# MSXII_SteeringWheelSchematic.net
KiCad netlist of a schematic drawn in Altium Designer
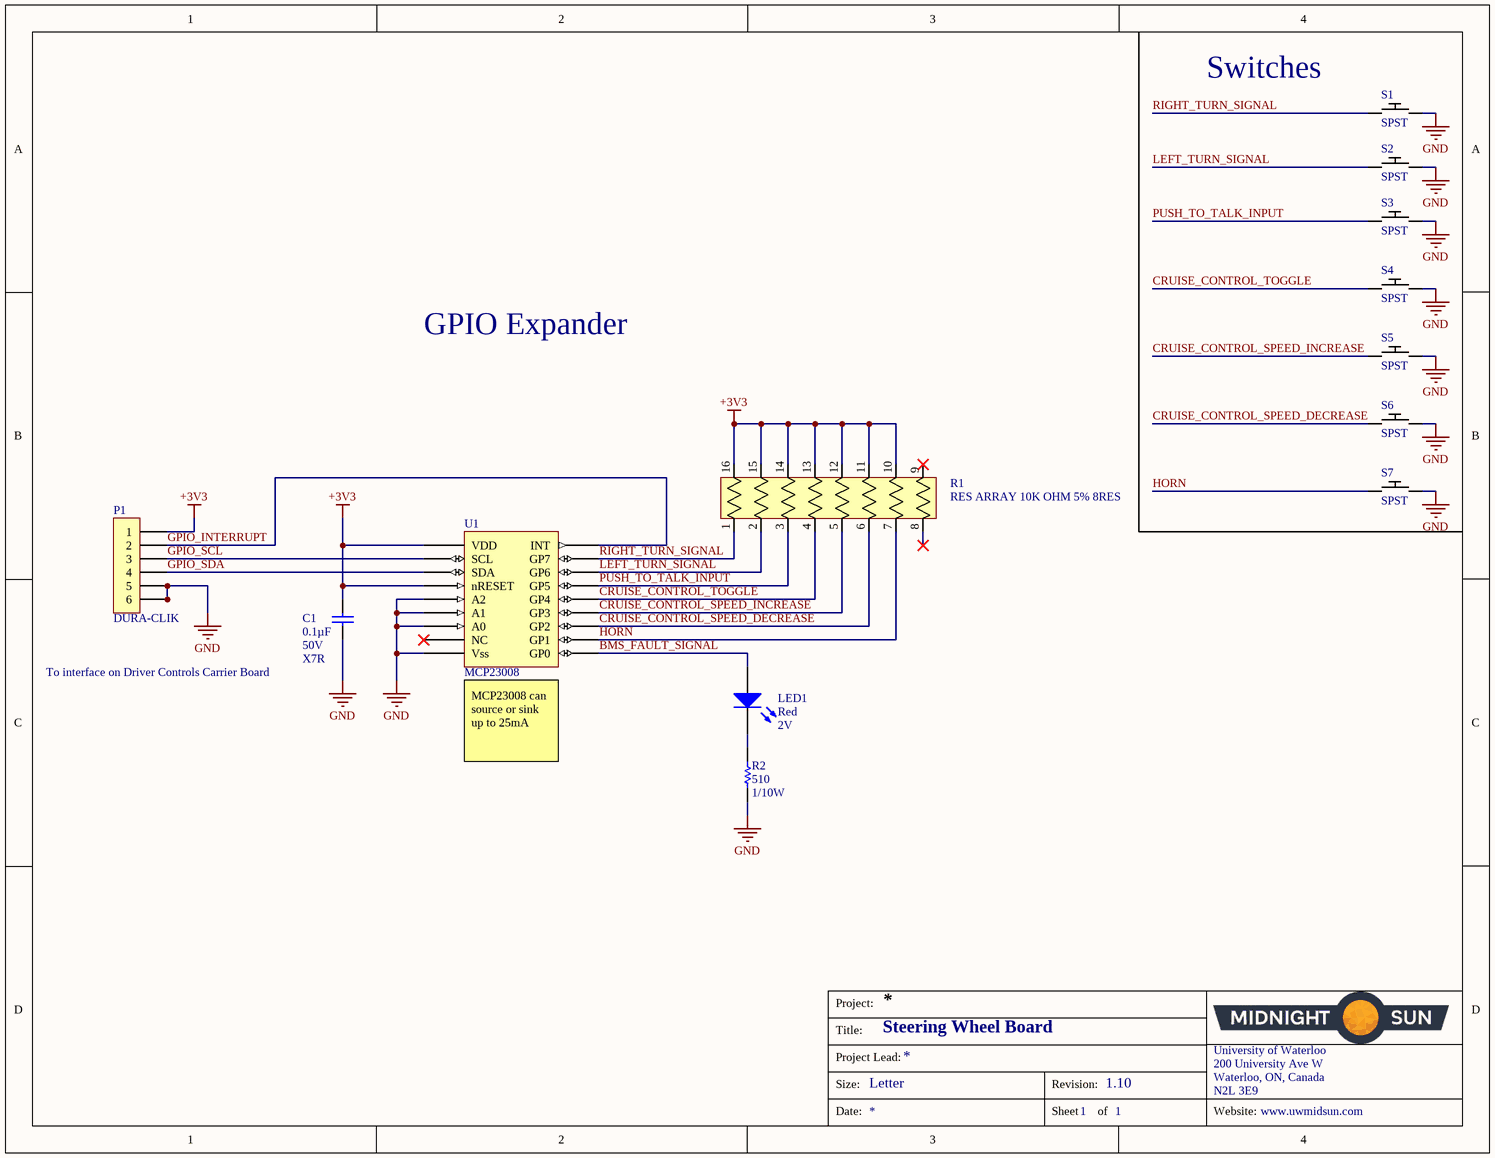
[diagram p0: MSXII_SteeringWheelSchematic.SchDoc]

(export (version "E")
  (design (tool "Eeschema 10.0.6"))
  (components
    (comp (ref "C1")
      (value "CAP CER 0.1UF 50V 10% X7R 0603")
      (footprint "CAP, 0603")
      (description "0.10µF ±10% 50V Ceramic Capacitor X7R 0603 (1608 Metric)")
      (fields
        (field (name "TOLERANCE") "±10%")
        (field (name "CAPACITANCE") "0.1µF")
        (field (name "VOLTAGE") "50V")
        (field (name "TEMPERATURE COEFFICIENT") "X7R")
      )
      (libsource (lib "Schematic Diagrams") (part "CAP CER 0.1UF 50V 10% X7R 0603"))
    )
    (comp (ref "LED1")
      (value "LED RED CLEAR 2V 0603")
      (footprint "LED_0603")
      (description "Red 631nm LED Indication - Discrete 2V 0603 (1608 Metric)")
      (fields
        (field (name "MANUFACTURER") "Wurth Electronics Inc.")
        (field (name "MANUFACTURER PART NUMBER") "150060RS75000")
        (field (name "COLOR") "Red")
        (field (name "VOLTAGE - FORWARD (VF) (TYP)") "2V")
      )
      (libsource (lib "Schematic Diagrams") (part "LED RED CLEAR 2V 0603"))
    )
    (comp (ref "P1")
      (value "DURA-CLIK")
      (footprint "CONN, 6POS DURA-CLIK VERT")
      (description "6 Positions Header, Shrouded Connector 0.079\" (2.00mm) Surface Mount, Vertical Tin")
      (fields (field (name "MANUFACTURER") "Molex") (field (name "MANUFACTURER PART NUMBER") "5600200820"))
      (libsource (lib "Schematic Diagrams") (part "CONN 6POS DURA-CLIK 0.079{dblquote}"))
    )
    (comp (ref "R1")
      (value "RES ARRAY 10K OHM 5% 8RES")
      (footprint "RES ARRAY, 8 POS 1506")
      (description "RES ARRAY SMD 10K 5% 62.5mW 1506")
      (fields
        (field (name "MANUFACTURER_PART_NUMBER") "EXB-2HV103JV")
        (field (name "MANUFACTURER") "Panasonic Electronic Components")
        (field (name "COPYRIGHT") "Copyright (C) 2015 Accelerated Designs. All rights reserved")
      )
      (libsource (lib "Schematic Diagrams") (part "RES ARRAY 10K OHM 5% 8RES EXB-2HV103JV"))
    )
    (comp (ref "R2")
      (value "RES 510 OHM 5% 1/10W 0603")
      (footprint "RES, 0603")
      (description "RES SMD 510 OHM 5% 1/10W 0603")
      (fields
        (field (name "TOLERANCE") "±5%")
        (field (name "RESISTANCE") "510")
        (field (name "POWER") "1/10W")
      )
      (libsource (lib "Schematic Diagrams") (part "RES 510 OHM 5% 1/10W 0603"))
    )
    (comp (ref "S1")
      (value "SPST")
      (footprint "SW SPST D6 SERIES")
      (description "Pushbutton Switch SPST-NO Keyswitch Through Hole D6 Series")
      (fields (field (name "MANUFACTURER") "C&K") (field (name "MANUFACTURER PART NUMBER") "D6R00 F2 LFS"))
      (libsource (lib "Schematic Diagrams") (part "SW SPST-NO 0.1A 32V D6 Series"))
    )
    (comp (ref "S2")
      (value "SPST")
      (footprint "SW SPST D6 SERIES")
      (description "Pushbutton Switch SPST-NO Keyswitch Through Hole D6 Series")
      (fields (field (name "MANUFACTURER") "C&K") (field (name "MANUFACTURER PART NUMBER") "D6R00 F2 LFS"))
      (libsource (lib "Schematic Diagrams") (part "SW SPST-NO 0.1A 32V D6 Series"))
    )
    (comp (ref "S3")
      (value "SPST")
      (footprint "SW SPST D6 SERIES")
      (description "Pushbutton Switch SPST-NO Keyswitch Through Hole D6 Series")
      (fields (field (name "MANUFACTURER") "C&K") (field (name "MANUFACTURER PART NUMBER") "D6R00 F2 LFS"))
      (libsource (lib "Schematic Diagrams") (part "SW SPST-NO 0.1A 32V D6 Series"))
    )
    (comp (ref "S4")
      (value "SPST")
      (footprint "SW SPST D6 SERIES")
      (description "Pushbutton Switch SPST-NO Keyswitch Through Hole D6 Series")
      (fields (field (name "MANUFACTURER") "C&K") (field (name "MANUFACTURER PART NUMBER") "D6R00 F2 LFS"))
      (libsource (lib "Schematic Diagrams") (part "SW SPST-NO 0.1A 32V D6 Series"))
    )
    (comp (ref "S5")
      (value "SPST")
      (footprint "SW SPST D6 SERIES")
      (description "Pushbutton Switch SPST-NO Keyswitch Through Hole D6 Series")
      (fields (field (name "MANUFACTURER") "C&K") (field (name "MANUFACTURER PART NUMBER") "D6R00 F2 LFS"))
      (libsource (lib "Schematic Diagrams") (part "SW SPST-NO 0.1A 32V D6 Series"))
    )
    (comp (ref "S6")
      (value "SPST")
      (footprint "SW SPST D6 SERIES")
      (description "Pushbutton Switch SPST-NO Keyswitch Through Hole D6 Series")
      (fields (field (name "MANUFACTURER") "C&K") (field (name "MANUFACTURER PART NUMBER") "D6R00 F2 LFS"))
      (libsource (lib "Schematic Diagrams") (part "SW SPST-NO 0.1A 32V D6 Series"))
    )
    (comp (ref "S7")
      (value "SPST")
      (footprint "SW SPST D6 SERIES")
      (description "Pushbutton Switch SPST-NO Keyswitch Through Hole D6 Series")
      (fields (field (name "MANUFACTURER") "C&K") (field (name "MANUFACTURER PART NUMBER") "D6R00 F2 LFS"))
      (libsource (lib "Schematic Diagrams") (part "SW SPST-NO 0.1A 32V D6 Series"))
    )
    (comp (ref "U1")
      (value "MCP23008")
      (footprint "IC 18SOIC")
      (description "MCP23008 I/O Expander 8B+1Int 18P SOIC")
      (fields
        (field (name "MANUFACTURER") "Microchip Technology")
        (field (name "MANUFACTURER PART NUMBER") "MCP23008T-E/SO")
      )
      (libsource (lib "Schematic Diagrams") (part "IC I/O EXPANDER I2C 8B 18SOIC"))
    )
  )
  (nets
    (net (code "1") (name "+3V3") (class "Default")
      (node (ref "C1") (pin "1") (pinfunction "1_1") (pintype "passive"))
      (node (ref "P1") (pin "1") (pinfunction "1_1") (pintype "passive"))
      (node (ref "R1") (pin "10") (pinfunction "10_10") (pintype "passive"))
      (node (ref "R1") (pin "11") (pinfunction "11_11") (pintype "passive"))
      (node (ref "R1") (pin "12") (pinfunction "12_12") (pintype "passive"))
      (node (ref "R1") (pin "13") (pinfunction "13_13") (pintype "passive"))
      (node (ref "R1") (pin "14") (pinfunction "14_14") (pintype "passive"))
      (node (ref "R1") (pin "15") (pinfunction "15_15") (pintype "passive"))
      (node (ref "R1") (pin "16") (pinfunction "16_16") (pintype "passive"))
      (node (ref "U1") (pin "18") (pinfunction "VDD_18") (pintype "power_in"))
      (node (ref "U1") (pin "6") (pinfunction "nRESET_6") (pintype "input"))
    )
    (net (code "2") (name "/BMS_FAULT_SIGNAL") (class "Default")
      (node (ref "LED1") (pin "1") (pinfunction "A_1") (pintype "passive"))
      (node (ref "U1") (pin "10") (pinfunction "GP0_10") (pintype "bidirectional"))
    )
    (net (code "3") (name "/CRUISE_CONTROL_SPEED_DECREASE") (class "Default")
      (node (ref "R1") (pin "6") (pinfunction "6_6") (pintype "passive"))
      (node (ref "S6") (pin "1") (pinfunction "1_1") (pintype "passive"))
      (node (ref "U1") (pin "12") (pinfunction "GP2_12") (pintype "bidirectional"))
    )
    (net (code "4") (name "/CRUISE_CONTROL_SPEED_INCREASE") (class "Default")
      (node (ref "R1") (pin "5") (pinfunction "5_5") (pintype "passive"))
      (node (ref "S5") (pin "1") (pinfunction "1_1") (pintype "passive"))
      (node (ref "U1") (pin "13") (pinfunction "GP3_13") (pintype "bidirectional"))
    )
    (net (code "5") (name "/CRUISE_CONTROL_TOGGLE") (class "Default")
      (node (ref "R1") (pin "4") (pinfunction "4_4") (pintype "passive"))
      (node (ref "S4") (pin "1") (pinfunction "1_1") (pintype "passive"))
      (node (ref "U1") (pin "14") (pinfunction "GP4_14") (pintype "bidirectional"))
    )
    (net (code "6") (name "/GPIO_INTERRUPT") (class "Default")
      (node (ref "P1") (pin "2") (pinfunction "2_2") (pintype "passive"))
      (node (ref "U1") (pin "8") (pinfunction "INT_8") (pintype "output"))
    )
    (net (code "7") (name "/GPIO_SCL") (class "Default")
      (node (ref "P1") (pin "3") (pinfunction "3_3") (pintype "passive"))
      (node (ref "U1") (pin "1") (pinfunction "SCL_1") (pintype "bidirectional"))
    )
    (net (code "8") (name "/GPIO_SDA") (class "Default")
      (node (ref "P1") (pin "4") (pinfunction "4_4") (pintype "passive"))
      (node (ref "U1") (pin "2") (pinfunction "SDA_2") (pintype "bidirectional"))
    )
    (net (code "9") (name "/HORN") (class "Default")
      (node (ref "R1") (pin "7") (pinfunction "7_7") (pintype "passive"))
      (node (ref "S7") (pin "1") (pinfunction "1_1") (pintype "passive"))
      (node (ref "U1") (pin "11") (pinfunction "GP1_11") (pintype "bidirectional"))
    )
    (net (code "10") (name "/LEFT_TURN_SIGNAL") (class "Default")
      (node (ref "R1") (pin "2") (pinfunction "2_2") (pintype "passive"))
      (node (ref "S2") (pin "1") (pinfunction "1_1") (pintype "passive"))
      (node (ref "U1") (pin "16") (pinfunction "GP6_16") (pintype "bidirectional"))
    )
    (net (code "11") (name "/PUSH_TO_TALK_INPUT") (class "Default")
      (node (ref "R1") (pin "3") (pinfunction "3_3") (pintype "passive"))
      (node (ref "S3") (pin "1") (pinfunction "1_1") (pintype "passive"))
      (node (ref "U1") (pin "15") (pinfunction "GP5_15") (pintype "bidirectional"))
    )
    (net (code "12") (name "/RIGHT_TURN_SIGNAL") (class "Default")
      (node (ref "R1") (pin "1") (pinfunction "1_1") (pintype "passive"))
      (node (ref "S1") (pin "1") (pinfunction "1_1") (pintype "passive"))
      (node (ref "U1") (pin "17") (pinfunction "GP7_17") (pintype "bidirectional"))
    )
    (net (code "13") (name "GND") (class "Default")
      (node (ref "C1") (pin "2") (pinfunction "2_2") (pintype "passive"))
      (node (ref "P1") (pin "5") (pinfunction "5_5") (pintype "passive"))
      (node (ref "P1") (pin "6") (pinfunction "6_6") (pintype "passive"))
      (node (ref "R2") (pin "2") (pinfunction "2_2") (pintype "passive"))
      (node (ref "S1") (pin "2") (pinfunction "2_2") (pintype "passive"))
      (node (ref "S2") (pin "2") (pinfunction "2_2") (pintype "passive"))
      (node (ref "S3") (pin "2") (pinfunction "2_2") (pintype "passive"))
      (node (ref "S4") (pin "2") (pinfunction "2_2") (pintype "passive"))
      (node (ref "S5") (pin "2") (pinfunction "2_2") (pintype "passive"))
      (node (ref "S6") (pin "2") (pinfunction "2_2") (pintype "passive"))
      (node (ref "S7") (pin "2") (pinfunction "2_2") (pintype "passive"))
      (node (ref "U1") (pin "3") (pinfunction "A2_3") (pintype "input"))
      (node (ref "U1") (pin "4") (pinfunction "A1_4") (pintype "input"))
      (node (ref "U1") (pin "5") (pinfunction "A0_5") (pintype "input"))
      (node (ref "U1") (pin "9") (pinfunction "Vss_9") (pintype "power_in"))
    )
    (net (code "14") (name "Net-(LED1-K)") (class "Default")
      (node (ref "LED1") (pin "2") (pinfunction "K_2") (pintype "passive"))
      (node (ref "R2") (pin "1") (pinfunction "1_1") (pintype "passive"))
    )
    (net (code "15") (name "unconnected-(R1-Pad8)") (class "Default")
      (node (ref "R1") (pin "8") (pinfunction "8_8") (pintype "passive+no_connect"))
    )
    (net (code "16") (name "unconnected-(R1-Pad9)") (class "Default")
      (node (ref "R1") (pin "9") (pinfunction "9_9") (pintype "passive+no_connect"))
    )
    (net (code "17") (name "unconnected-(U1-NC-Pad7)") (class "Default")
      (node (ref "U1") (pin "7") (pinfunction "NC_7") (pintype "passive+no_connect"))
    )
  )
)
